# MCU.net
KiCad netlist of a schematic drawn in Altium Designer
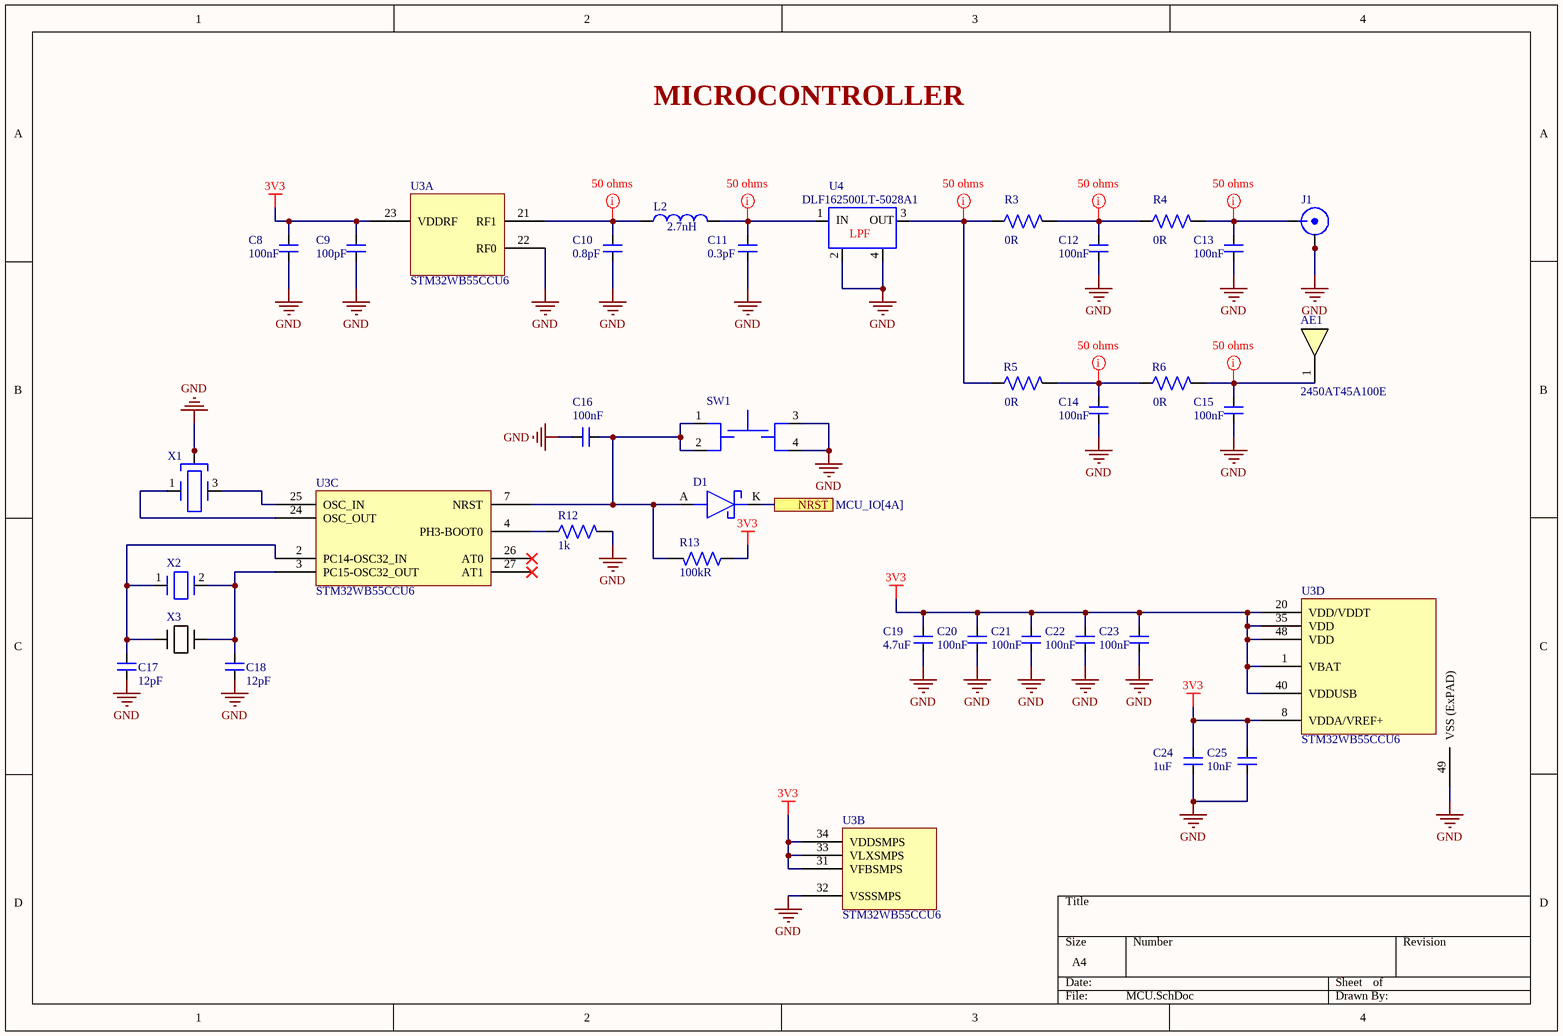
[diagram p0: MCU.SchDoc]

(export (version "E")
  (design (tool "Eeschema 10.0.6"))
  (components
    (comp (ref "AE1")
      (value "2450AT45A100E")
      (footprint "2450AT45A100E")
      (description "Antenna Ceramic 2.2dBi Gain 2500MHz 2-Pin T/R / ANTENNA CHIP 2.4GHZ")
      (fields (field (name "MANUFACTURER") "Johanson"))
      (libsource (lib "Schlib1") (part "2450AT45A100E"))
    )
    (comp (ref "C8")
      (value "100nF")
      (footprint "C0402")
      (description "Multilayer Ceramic Capacitor, 0.1 uF, 16 V, ï¿½ 10%, X7R, 0402 [1005 Metric]")
      (fields
        (field (name "MANUFACTURER") "KEMET")
        (field (name "MANUFACTURER PART NUMBER") "C0402C104K4RACTU")
      )
      (libsource (lib "Schlib1") (part "C0402C104K4RACTU"))
    )
    (comp (ref "C9")
      (value "100pF")
      (footprint "C0402")
      (description "Multilayer Ceramic Capacitor, 100 pF, 50 V, ï¿½ 5%, C0G (NP0), 0402 [1005 Metric]")
      (fields
        (field (name "MANUFACTURER") "Murata")
        (field (name "MANUFACTURER PART NUMBER") "GCM1555C1H101JA16D")
      )
      (libsource (lib "Schlib1") (part "GCM1555C1H101JA16D"))
    )
    (comp (ref "C10")
      (value "0.8pF")
      (footprint "C0402")
      (description "Multilayer Ceramic Capacitor, 0.8 pF, 50 V, ï¿½ 0.1pF, C0G (NP0), 0402 [1005 Metric]")
      (fields
        (field (name "MANUFACTURER") "Murata")
        (field (name "MANUFACTURER PART NUMBER") "GRM1555C1HR80BA01D")
      )
      (libsource (lib "Schlib1") (part "GRM1555C1HR80BA01D"))
    )
    (comp (ref "C11")
      (value "0.3pF")
      (footprint "C0402")
      (description "Cap Ceramic 0.3pF 50V C0G 0.05pF Pad SMD 0402 125°C T/R")
      (fields
        (field (name "MANUFACTURER") "Murata")
        (field (name "MANUFACTURER PART NUMBER") "GRM1555C1HR30WA01D")
      )
      (libsource (lib "Schlib1") (part "GRM1555C1HR30WA01D"))
    )
    (comp (ref "C12")
      (value "100nF")
      (footprint "C0402")
      (description "Multilayer Ceramic Capacitor, 0.1 uF, 16 V, ï¿½ 10%, X7R, 0402 [1005 Metric]")
      (fields
        (field (name "MANUFACTURER") "KEMET")
        (field (name "MANUFACTURER PART NUMBER") "C0402C104K4RACTU")
      )
      (libsource (lib "Schlib1") (part "C0402C104K4RACTU"))
    )
    (comp (ref "C13")
      (value "100nF")
      (footprint "C0402")
      (description "Multilayer Ceramic Capacitor, 0.1 uF, 16 V, ï¿½ 10%, X7R, 0402 [1005 Metric]")
      (fields
        (field (name "MANUFACTURER") "KEMET")
        (field (name "MANUFACTURER PART NUMBER") "C0402C104K4RACTU")
      )
      (libsource (lib "Schlib1") (part "C0402C104K4RACTU"))
    )
    (comp (ref "C14")
      (value "100nF")
      (footprint "C0402")
      (description "Multilayer Ceramic Capacitor, 0.1 uF, 16 V, ï¿½ 10%, X7R, 0402 [1005 Metric]")
      (fields
        (field (name "MANUFACTURER") "KEMET")
        (field (name "MANUFACTURER PART NUMBER") "C0402C104K4RACTU")
      )
      (libsource (lib "Schlib1") (part "C0402C104K4RACTU"))
    )
    (comp (ref "C15")
      (value "100nF")
      (footprint "C0402")
      (description "Multilayer Ceramic Capacitor, 0.1 uF, 16 V, ï¿½ 10%, X7R, 0402 [1005 Metric]")
      (fields
        (field (name "MANUFACTURER") "KEMET")
        (field (name "MANUFACTURER PART NUMBER") "C0402C104K4RACTU")
      )
      (libsource (lib "Schlib1") (part "C0402C104K4RACTU"))
    )
    (comp (ref "C16")
      (value "100nF")
      (footprint "C0402")
      (description "Multilayer Ceramic Capacitor, 0.1 uF, 16 V, ï¿½ 10%, X7R, 0402 [1005 Metric]")
      (fields
        (field (name "MANUFACTURER") "KEMET")
        (field (name "MANUFACTURER PART NUMBER") "C0402C104K4RACTU")
      )
      (libsource (lib "Schlib1") (part "C0402C104K4RACTU"))
    )
    (comp (ref "C17")
      (value "12pF")
      (footprint "C0402")
      (description "Multilayer Ceramic Capacitor, 12 pF, 50 V, ï¿½ 5%, C0G (NP0), 0402 [1005 Metric]")
      (fields
        (field (name "MANUFACTURER") "KEMET")
        (field (name "MANUFACTURER PART NUMBER") "C0402C120J5GACTU")
      )
      (libsource (lib "Schlib1") (part "C0402C120J5GACTU"))
    )
    (comp (ref "C18")
      (value "12pF")
      (footprint "C0402")
      (description "Multilayer Ceramic Capacitor, 12 pF, 50 V, ï¿½ 5%, C0G (NP0), 0402 [1005 Metric]")
      (fields
        (field (name "MANUFACTURER") "KEMET")
        (field (name "MANUFACTURER PART NUMBER") "C0402C120J5GACTU")
      )
      (libsource (lib "Schlib1") (part "C0402C120J5GACTU"))
    )
    (comp (ref "C19")
      (value "4.7uF")
      (footprint "C1210")
      (description "Multilayer Ceramic Capacitor, 4.7 uF, 100 V, ï¿½ 10%, X7S, 1210 [3225 Metric]")
      (fields
        (field (name "MANUFACTURER") "TDK")
        (field (name "MANUFACTURER PART NUMBER") "CGA6M3X7S2A475K200AB")
      )
      (libsource (lib "Schlib1") (part "CGA6M3X7S2A475K200AB"))
    )
    (comp (ref "C20")
      (value "100nF")
      (footprint "C0402")
      (description "Multilayer Ceramic Capacitor, 0.1 uF, 16 V, ï¿½ 10%, X7R, 0402 [1005 Metric]")
      (fields
        (field (name "MANUFACTURER") "KEMET")
        (field (name "MANUFACTURER PART NUMBER") "C0402C104K4RACTU")
      )
      (libsource (lib "Schlib1") (part "C0402C104K4RACTU"))
    )
    (comp (ref "C21")
      (value "100nF")
      (footprint "C0402")
      (description "Multilayer Ceramic Capacitor, 0.1 uF, 16 V, ï¿½ 10%, X7R, 0402 [1005 Metric]")
      (fields
        (field (name "MANUFACTURER") "KEMET")
        (field (name "MANUFACTURER PART NUMBER") "C0402C104K4RACTU")
      )
      (libsource (lib "Schlib1") (part "C0402C104K4RACTU"))
    )
    (comp (ref "C22")
      (value "100nF")
      (footprint "C0402")
      (description "Multilayer Ceramic Capacitor, 0.1 uF, 16 V, ï¿½ 10%, X7R, 0402 [1005 Metric]")
      (fields
        (field (name "MANUFACTURER") "KEMET")
        (field (name "MANUFACTURER PART NUMBER") "C0402C104K4RACTU")
      )
      (libsource (lib "Schlib1") (part "C0402C104K4RACTU"))
    )
    (comp (ref "C23")
      (value "100nF")
      (footprint "C0402")
      (description "Multilayer Ceramic Capacitor, 0.1 uF, 16 V, ï¿½ 10%, X7R, 0402 [1005 Metric]")
      (fields
        (field (name "MANUFACTURER") "KEMET")
        (field (name "MANUFACTURER PART NUMBER") "C0402C104K4RACTU")
      )
      (libsource (lib "Schlib1") (part "C0402C104K4RACTU"))
    )
    (comp (ref "C24")
      (value "1uF")
      (footprint "C0402")
      (description "Multilayer Ceramic Capacitor, 1 uF, 10 V, ± 10%, X6S, 0402 [1005 Metric]")
      (fields
        (field (name "MANUFACTURER") "TDK")
        (field (name "MANUFACTURER PART NUMBER") "CGB2A1X6S1A105K033BC")
      )
      (libsource (lib "Schlib1") (part "CGB2A1X6S1A105K033BC"))
    )
    (comp (ref "C25")
      (value "10nF")
      (footprint "C0402")
      (description "Multilayer Ceramic Capacitor, 0.01 uF, 50 V, ï¿½ 10%, X7R, 0402 [1005 Metric]")
      (fields
        (field (name "MANUFACTURER") "Yageo")
        (field (name "MANUFACTURER PART NUMBER") "CC0402KRX7R9BB103")
      )
      (libsource (lib "Schlib1") (part "CC0402KRX7R9BB103"))
    )
    (comp (ref "D1")
      (value "BAT54GWJ")
      (footprint "SOD123")
      (description "Schottky Diode, Sngl, 30V, 0.2A, Sod-123 Rohs Compliant: Yes ¦Nexperia BAT54GWJ")
      (fields (field (name "MANUFACTURER") "Nexperia"))
      (libsource (lib "Schlib1") (part "BAT54GWJ"))
    )
    (comp (ref "J1")
      (value "RSP-122811-01")
      (footprint "U.FL-R-SMT-1(10)")
      (description "RF MHF Connector, 1 Contact(s), Male, Board Mount, Surface Mount Terminal, Receptacle")
      (fields (field (name "MANUFACTURER") "Samtec"))
      (libsource (lib "Schlib1") (part "RSP-122811-01"))
    )
    (comp (ref "L2")
      (value "LQG15HS2N7S02D")
      (footprint "L0402")
      (description "Inductor RF Chip Multi-Layer 2.7nH 0.3nH 100MHz 8Q-Factor Air 300mA 150mOhm DCR 0402 T/R")
      (fields (field (name "MANUFACTURER") "Murata"))
      (libsource (lib "Schlib1") (part "LQG15HS2N7S02D"))
    )
    (comp (ref "R3")
      (value "0R")
      (footprint "R0402")
      (description "GENERAL PURPOSE CHIP RESISTOR Metal Glaze/thick Film, 0.0625W, 0ohm, Surface Mount, 0402")
      (fields
        (field (name "MANUFACTURER") "Yageo")
        (field (name "MANUFACTURER PART NUMBER") "RC0402JR-070RL")
      )
      (libsource (lib "Schlib1") (part "RC0402JR-070RL"))
    )
    (comp (ref "R4")
      (value "0R")
      (footprint "R0402")
      (description "GENERAL PURPOSE CHIP RESISTOR Metal Glaze/thick Film, 0.0625W, 0ohm, Surface Mount, 0402")
      (fields
        (field (name "MANUFACTURER") "Yageo")
        (field (name "MANUFACTURER PART NUMBER") "RC0402JR-070RL")
      )
      (libsource (lib "Schlib1") (part "RC0402JR-070RL"))
    )
    (comp (ref "R5")
      (value "0R")
      (footprint "R0402")
      (description "GENERAL PURPOSE CHIP RESISTOR Metal Glaze/thick Film, 0.0625W, 0ohm, Surface Mount, 0402")
      (fields
        (field (name "MANUFACTURER") "Yageo")
        (field (name "MANUFACTURER PART NUMBER") "RC0402JR-070RL")
      )
      (libsource (lib "Schlib1") (part "RC0402JR-070RL"))
    )
    (comp (ref "R6")
      (value "0R")
      (footprint "R0402")
      (description "GENERAL PURPOSE CHIP RESISTOR Metal Glaze/thick Film, 0.0625W, 0ohm, Surface Mount, 0402")
      (fields
        (field (name "MANUFACTURER") "Yageo")
        (field (name "MANUFACTURER PART NUMBER") "RC0402JR-070RL")
      )
      (libsource (lib "Schlib1") (part "RC0402JR-070RL"))
    )
    (comp (ref "R12")
      (value "1k")
      (footprint "R0402")
      (description "SMD Chip Resistor 1 Kohm ½ 1% 62.5 Mw 0402 [1005 Metric] Thick Film General Purpose")
      (fields
        (field (name "MANUFACTURER") "Yageo")
        (field (name "MANUFACTURER PART NUMBER") "RC0402FR-071KL")
      )
      (libsource (lib "Schlib1") (part "RC0402FR-071KL"))
    )
    (comp (ref "R13")
      (value "100kR")
      (footprint "R0402")
      (description "SMD Chip Resistor, 100 Kohm, ½ 5%, 62.5 Mw, 0402 [1005 Metric], Thick Film, General Purpose")
      (fields
        (field (name "MANUFACTURER") "Yageo")
        (field (name "MANUFACTURER PART NUMBER") "RC0402JR-07100KL")
      )
      (libsource (lib "Schlib1") (part "RC0402JR-07100KL"))
    )
    (comp (ref "SW1")
      (value "TS02-66-130-BK-260-LCR-D")
      (footprint "BUTTON")
      (fields (field (name "MANUFACTURER") "Same Sky"))
      (libsource (lib "Schlib1") (part "TS02-66-130-BK-260-LCR-D"))
    )
    (comp (ref "U3")
      (value "STM32WB55CCU6")
      (footprint "WB55")
      (description "MCU 32-Bit STM32WB55 ARM Cortex-M4F RISC 256KB Flash 1.71V to 3.6V 48-Pin UFQFPN T/R")
      (fields (field (name "MANUFACTURER") "STMicroelectronics"))
      (libsource (lib "Schlib1") (part "STM32WB55CCU6"))
    )
    (comp (ref "U4")
      (value "DLF162500LT-5028A1")
      (footprint "4PIN_LPF")
      (description "FILTER, LOW PASS, 2.4GHz to 2.5GHz; Filter Type: Low Pass; Pass Band Frequency: 2.")
      (fields (field (name "MANUFACTURER") "TDK"))
      (libsource (lib "Schlib1") (part "DLF162500LT-5028A1"))
    )
    (comp (ref "X1")
      (value "NX2016SA-32M-EXS00A-CS06465")
      (footprint "XTAL32MHZ")
      (description "Crystal 32.0000MHZ 10PF SMD")
      (fields (field (name "MANUFACTURER") "NDK"))
      (libsource (lib "Schlib1") (part "NX2016SA-32M-EXS00A-CS06465"))
    )
    (comp (ref "X2")
      (value "NX2012SA-32.768K-STD-MUB-1")
      (footprint "NX2012SA")
      (description "Parallel - Fundamental Quartz Crystal, 0.032768MHz Nom")
      (fields (field (name "MANUFACTURER") "NDK") (field (name "TOLERANCE") "0.002%"))
      (libsource (lib "Schlib1") (part "NX2012SA-32.768K-STD-MUB-1"))
    )
    (comp (ref "X3")
      (value "ECS-.327-12.5-17X-TR")
      (footprint "CRI_306")
      (description "Crystal 0.032768MHz ±20ppm (Tol) 12.5pF FUND 50000Ohm 4-Pin SMD T/R")
      (fields (field (name "MANUFACTURER") "ECS International") (field (name "TOLERANCE") "20ppm"))
      (libsource (lib "Schlib1") (part "ECS-.327-12.5-17X-TR"))
    )
  )
  (nets
    (net (code "1") (name "/NRST") (class "Default")
      (node (ref "D1") (pin "K") (pinfunction "1_K") (pintype "passive"))
    )
    (net (code "2") (name "3V3") (class "Default")
      (node (ref "C19") (pin "2") (pinfunction "2_2") (pintype "passive"))
      (node (ref "C20") (pin "2") (pinfunction "2_2") (pintype "passive"))
      (node (ref "C21") (pin "2") (pinfunction "2_2") (pintype "passive"))
      (node (ref "C22") (pin "2") (pinfunction "2_2") (pintype "passive"))
      (node (ref "C23") (pin "2") (pinfunction "2_2") (pintype "passive"))
      (node (ref "C24") (pin "2") (pinfunction "2_2") (pintype "passive"))
      (node (ref "C25") (pin "2") (pinfunction "2_2") (pintype "passive"))
      (node (ref "C8") (pin "2") (pinfunction "2_2") (pintype "passive"))
      (node (ref "C9") (pin "2") (pinfunction "2_2") (pintype "passive"))
      (node (ref "R13") (pin "1") (pinfunction "1_1") (pintype "passive"))
      (node (ref "U3") (pin "1") (pinfunction "VBAT_1") (pintype "passive"))
      (node (ref "U3") (pin "20") (pinfunction "VDD/VDDT_20") (pintype "passive"))
      (node (ref "U3") (pin "23") (pinfunction "VDDRF_23") (pintype "passive"))
      (node (ref "U3") (pin "31") (pinfunction "VFBSMPS_31") (pintype "passive"))
      (node (ref "U3") (pin "33") (pinfunction "VLXSMPS_33") (pintype "passive"))
      (node (ref "U3") (pin "34") (pinfunction "VDDSMPS_34") (pintype "passive"))
      (node (ref "U3") (pin "35") (pinfunction "VDD_35") (pintype "passive"))
      (node (ref "U3") (pin "40") (pinfunction "VDDUSB_40") (pintype "passive"))
      (node (ref "U3") (pin "48") (pinfunction "VDD_48") (pintype "passive"))
      (node (ref "U3") (pin "8") (pinfunction "VDDA/VREF+_8") (pintype "passive"))
    )
    (net (code "3") (name "GND") (class "Default")
      (node (ref "C10") (pin "1") (pinfunction "1_1") (pintype "passive"))
      (node (ref "C11") (pin "1") (pinfunction "1_1") (pintype "passive"))
      (node (ref "C12") (pin "1") (pinfunction "1_1") (pintype "passive"))
      (node (ref "C13") (pin "1") (pinfunction "1_1") (pintype "passive"))
      (node (ref "C14") (pin "1") (pinfunction "1_1") (pintype "passive"))
      (node (ref "C15") (pin "1") (pinfunction "1_1") (pintype "passive"))
      (node (ref "C16") (pin "2") (pinfunction "2_2") (pintype "passive"))
      (node (ref "C17") (pin "1") (pinfunction "1_1") (pintype "passive"))
      (node (ref "C18") (pin "2") (pinfunction "2_2") (pintype "passive"))
      (node (ref "C19") (pin "1") (pinfunction "1_1") (pintype "passive"))
      (node (ref "C20") (pin "1") (pinfunction "1_1") (pintype "passive"))
      (node (ref "C21") (pin "1") (pinfunction "1_1") (pintype "passive"))
      (node (ref "C22") (pin "1") (pinfunction "1_1") (pintype "passive"))
      (node (ref "C23") (pin "1") (pinfunction "1_1") (pintype "passive"))
      (node (ref "C24") (pin "1") (pinfunction "1_1") (pintype "passive"))
      (node (ref "C25") (pin "1") (pinfunction "1_1") (pintype "passive"))
      (node (ref "C8") (pin "1") (pinfunction "1_1") (pintype "passive"))
      (node (ref "C9") (pin "1") (pinfunction "1_1") (pintype "passive"))
      (node (ref "J1") (pin "2") (pinfunction "2_2") (pintype "passive"))
      (node (ref "J1") (pin "3") (pinfunction "3_3") (pintype "passive"))
      (node (ref "R12") (pin "2") (pinfunction "2_2") (pintype "passive"))
      (node (ref "SW1") (pin "3") (pinfunction "3_3") (pintype "passive"))
      (node (ref "SW1") (pin "4") (pinfunction "4_4") (pintype "passive"))
      (node (ref "U3") (pin "22") (pinfunction "RF0_22") (pintype "passive"))
      (node (ref "U3") (pin "32") (pinfunction "VSSSMPS_32") (pintype "passive"))
      (node (ref "U3") (pin "49") (pinfunction "VSS_(ExPAD)_49") (pintype "passive"))
      (node (ref "U4") (pin "2") (pinfunction "2_2") (pintype "passive"))
      (node (ref "U4") (pin "4") (pinfunction "4_4") (pintype "passive"))
      (node (ref "X1") (pin "2") (pinfunction "2_2") (pintype "passive"))
      (node (ref "X1") (pin "4") (pinfunction "4_4") (pintype "passive"))
    )
    (net (code "4") (name "Net-(AE1-Feeding_Point)") (class "Default")
      (node (ref "AE1") (pin "1") (pinfunction "Feeding_Point_1") (pintype "passive"))
      (node (ref "C15") (pin "2") (pinfunction "2_2") (pintype "passive"))
      (node (ref "R6") (pin "2") (pinfunction "2_2") (pintype "passive"))
    )
    (net (code "5") (name "Net-(C11-Pad2)") (class "Default")
      (node (ref "C11") (pin "2") (pinfunction "2_2") (pintype "passive"))
      (node (ref "L2") (pin "2") (pinfunction "2_2") (pintype "passive"))
      (node (ref "U4") (pin "1") (pinfunction "1_1") (pintype "passive"))
    )
    (net (code "6") (name "Net-(C12-Pad2)") (class "Default")
      (node (ref "C12") (pin "2") (pinfunction "2_2") (pintype "passive"))
      (node (ref "R3") (pin "2") (pinfunction "2_2") (pintype "passive"))
      (node (ref "R4") (pin "1") (pinfunction "1_1") (pintype "passive"))
    )
    (net (code "7") (name "Net-(C13-Pad2)") (class "Default")
      (node (ref "C13") (pin "2") (pinfunction "2_2") (pintype "passive"))
      (node (ref "J1") (pin "1") (pinfunction "1_1") (pintype "passive"))
      (node (ref "R4") (pin "2") (pinfunction "2_2") (pintype "passive"))
    )
    (net (code "8") (name "Net-(C14-Pad2)") (class "Default")
      (node (ref "C14") (pin "2") (pinfunction "2_2") (pintype "passive"))
      (node (ref "R5") (pin "2") (pinfunction "2_2") (pintype "passive"))
      (node (ref "R6") (pin "1") (pinfunction "1_1") (pintype "passive"))
    )
    (net (code "9") (name "Net-(D1-2)") (class "Default")
      (node (ref "C16") (pin "1") (pinfunction "1_1") (pintype "passive"))
      (node (ref "D1") (pin "A") (pinfunction "2_A") (pintype "passive"))
      (node (ref "R13") (pin "2") (pinfunction "2_2") (pintype "passive"))
      (node (ref "SW1") (pin "1") (pinfunction "1_1") (pintype "passive"))
      (node (ref "SW1") (pin "2") (pinfunction "2_2") (pintype "passive"))
      (node (ref "U3") (pin "7") (pinfunction "NRST_7") (pintype "passive"))
    )
    (net (code "10") (name "Net-(R3-Pad1)") (class "Default")
      (node (ref "R3") (pin "1") (pinfunction "1_1") (pintype "passive"))
      (node (ref "R5") (pin "1") (pinfunction "1_1") (pintype "passive"))
      (node (ref "U4") (pin "3") (pinfunction "3_3") (pintype "passive"))
    )
    (net (code "11") (name "Net-(U3A-RF1)") (class "Default")
      (node (ref "C10") (pin "2") (pinfunction "2_2") (pintype "passive"))
      (node (ref "L2") (pin "1") (pinfunction "1_1") (pintype "passive"))
      (node (ref "U3") (pin "21") (pinfunction "RF1_21") (pintype "passive"))
    )
    (net (code "12") (name "Net-(U3C-OSC_IN)") (class "Default")
      (node (ref "U3") (pin "25") (pinfunction "OSC_IN_25") (pintype "passive"))
      (node (ref "X1") (pin "3") (pinfunction "3_3") (pintype "passive"))
    )
    (net (code "13") (name "Net-(U3C-OSC_OUT)") (class "Default")
      (node (ref "U3") (pin "24") (pinfunction "OSC_OUT_24") (pintype "passive"))
      (node (ref "X1") (pin "1") (pinfunction "1_1") (pintype "passive"))
    )
    (net (code "14") (name "Net-(U3C-PC14-OSC32_IN)") (class "Default")
      (node (ref "C17") (pin "2") (pinfunction "2_2") (pintype "passive"))
      (node (ref "U3") (pin "2") (pinfunction "PC14-OSC32_IN_2") (pintype "passive"))
      (node (ref "X2") (pin "1") (pinfunction "1_1") (pintype "passive"))
      (node (ref "X3") (pin "1") (pinfunction "1_1") (pintype "passive"))
    )
    (net (code "15") (name "Net-(U3C-PC15-OSC32_OUT)") (class "Default")
      (node (ref "C18") (pin "1") (pinfunction "1_1") (pintype "passive"))
      (node (ref "U3") (pin "3") (pinfunction "PC15-OSC32_OUT_3") (pintype "passive"))
      (node (ref "X2") (pin "2") (pinfunction "2_2") (pintype "passive"))
      (node (ref "X3") (pin "4") (pinfunction "4_4") (pintype "passive"))
    )
    (net (code "16") (name "Net-(U3C-PH3-BOOT0)") (class "Default")
      (node (ref "R12") (pin "1") (pinfunction "1_1") (pintype "passive"))
      (node (ref "U3") (pin "4") (pinfunction "PH3-BOOT0_4") (pintype "passive"))
    )
    (net (code "17") (name "unconnected-(U3C-AT0-Pad26)") (class "Default")
      (node (ref "U3") (pin "26") (pinfunction "AT0_26") (pintype "passive+no_connect"))
    )
    (net (code "18") (name "unconnected-(U3C-AT1-Pad27)") (class "Default")
      (node (ref "U3") (pin "27") (pinfunction "AT1_27") (pintype "passive+no_connect"))
    )
  )
)
